# bicicletta-battery-sensor.net
KiCad netlist of a schematic drawn in EAGLE
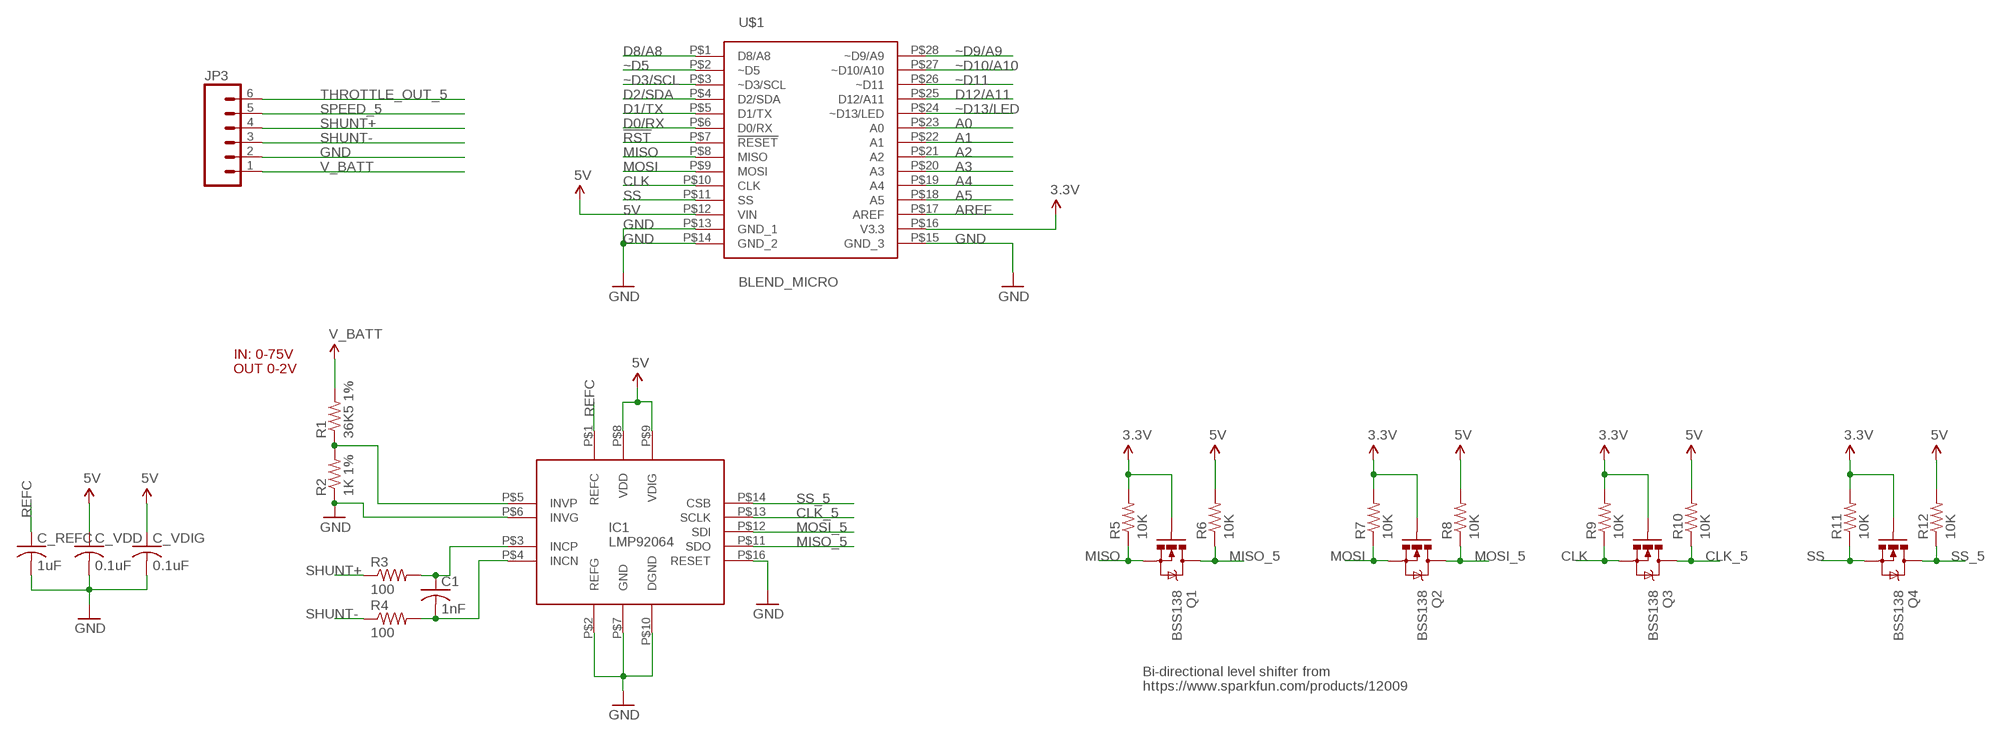
[diagram p0: schematic, sheet 1]

(export (version "E")
  (design (tool "Eeschema 10.0.6"))
  (components
    (comp (ref "C1")
      (value "1nF")
      (footprint "eagle-import:C0603")
      (libsource (lib "eagle-import") (part "C-USC0603"))
    )
    (comp (ref "C_REFC")
      (value "1uF")
      (footprint "eagle-import:C0603")
      (libsource (lib "eagle-import") (part "C-USC0603"))
    )
    (comp (ref "C_VDD")
      (value "0.1uF")
      (footprint "eagle-import:C0603")
      (libsource (lib "eagle-import") (part "C-USC0603"))
    )
    (comp (ref "C_VDIG")
      (value "0.1uF")
      (footprint "eagle-import:C0603")
      (libsource (lib "eagle-import") (part "C-USC0603"))
    )
    (comp (ref "IC1")
      (value "LMP92064")
      (footprint "eagle-import:WSON-16")
      (libsource (lib "eagle-import") (part "LMP92064"))
    )
    (comp (ref "JP3")
      (value "M06SIP")
      (footprint "eagle-import:1X06")
      (libsource (lib "eagle-import") (part "M06SIP"))
    )
    (comp (ref "Q1")
      (value "BSS138")
      (footprint "eagle-import:SOT23-3")
      (libsource (lib "eagle-import") (part "MOSFET-NCHANNELBSS138"))
    )
    (comp (ref "Q2")
      (value "BSS138")
      (footprint "eagle-import:SOT23-3")
      (libsource (lib "eagle-import") (part "MOSFET-NCHANNELBSS138"))
    )
    (comp (ref "Q3")
      (value "BSS138")
      (footprint "eagle-import:SOT23-3")
      (libsource (lib "eagle-import") (part "MOSFET-NCHANNELBSS138"))
    )
    (comp (ref "Q4")
      (value "BSS138")
      (footprint "eagle-import:SOT23-3")
      (libsource (lib "eagle-import") (part "MOSFET-NCHANNELBSS138"))
    )
    (comp (ref "R1")
      (value "36K5 1%")
      (footprint "eagle-import:R0603")
      (libsource (lib "eagle-import") (part "R-US_R0603"))
    )
    (comp (ref "R2")
      (value "1K 1%")
      (footprint "eagle-import:R0603")
      (libsource (lib "eagle-import") (part "R-US_R0603"))
    )
    (comp (ref "R3")
      (value "100")
      (footprint "eagle-import:R0603")
      (libsource (lib "eagle-import") (part "R-US_R0603"))
    )
    (comp (ref "R4")
      (value "100")
      (footprint "eagle-import:R0603")
      (libsource (lib "eagle-import") (part "R-US_R0603"))
    )
    (comp (ref "R5")
      (value "10K")
      (footprint "eagle-import:R0603")
      (libsource (lib "eagle-import") (part "R-US_R0603"))
    )
    (comp (ref "R6")
      (value "10K")
      (footprint "eagle-import:R0603")
      (libsource (lib "eagle-import") (part "R-US_R0603"))
    )
    (comp (ref "R7")
      (value "10K")
      (footprint "eagle-import:R0603")
      (libsource (lib "eagle-import") (part "R-US_R0603"))
    )
    (comp (ref "R8")
      (value "10K")
      (footprint "eagle-import:R0603")
      (libsource (lib "eagle-import") (part "R-US_R0603"))
    )
    (comp (ref "R9")
      (value "10K")
      (footprint "eagle-import:R0603")
      (libsource (lib "eagle-import") (part "R-US_R0603"))
    )
    (comp (ref "R10")
      (value "10K")
      (footprint "eagle-import:R0603")
      (libsource (lib "eagle-import") (part "R-US_R0603"))
    )
    (comp (ref "R11")
      (value "10K")
      (footprint "eagle-import:R0603")
      (libsource (lib "eagle-import") (part "R-US_R0603"))
    )
    (comp (ref "R12")
      (value "10K")
      (footprint "eagle-import:R0603")
      (libsource (lib "eagle-import") (part "R-US_R0603"))
    )
    (comp (ref "U$1")
      (value "BLEND_MICRO")
      (footprint "eagle-import:BLEND_MICRO")
      (libsource (lib "eagle-import") (part "BLEND_MICRO"))
    )
  )
  (nets
    (net (code "1") (name "/A0") (class "Default")
      (node (ref "U$1") (pin "P$23") (pinfunction "A0_P$23") (pintype "bidirectional"))
    )
    (net (code "2") (name "/A1") (class "Default")
      (node (ref "U$1") (pin "P$22") (pinfunction "A1_P$22") (pintype "bidirectional"))
    )
    (net (code "3") (name "/A2") (class "Default")
      (node (ref "U$1") (pin "P$21") (pinfunction "A2_P$21") (pintype "bidirectional"))
    )
    (net (code "4") (name "/A3") (class "Default")
      (node (ref "U$1") (pin "P$20") (pinfunction "A3_P$20") (pintype "bidirectional"))
    )
    (net (code "5") (name "/A4") (class "Default")
      (node (ref "U$1") (pin "P$19") (pinfunction "A4_P$19") (pintype "bidirectional"))
    )
    (net (code "6") (name "/A5") (class "Default")
      (node (ref "U$1") (pin "P$18") (pinfunction "A5_P$18") (pintype "bidirectional"))
    )
    (net (code "7") (name "/AREF") (class "Default")
      (node (ref "U$1") (pin "P$17") (pinfunction "AREF_P$17") (pintype "bidirectional"))
    )
    (net (code "8") (name "/CLK") (class "Default")
      (node (ref "Q3") (pin "2") (pinfunction "S_2") (pintype "passive"))
      (node (ref "R9") (pin "1") (pinfunction "1_1") (pintype "passive"))
      (node (ref "U$1") (pin "P$10") (pinfunction "CLK_P$10") (pintype "bidirectional"))
    )
    (net (code "9") (name "/CLK_5") (class "Default")
      (node (ref "IC1") (pin "P$13") (pinfunction "SCLK_P$13") (pintype "bidirectional"))
      (node (ref "Q3") (pin "3") (pinfunction "D_3") (pintype "passive"))
      (node (ref "R10") (pin "1") (pinfunction "1_1") (pintype "passive"))
    )
    (net (code "10") (name "/D0{slash}RX") (class "Default")
      (node (ref "U$1") (pin "P$6") (pinfunction "D0/RX_P$6") (pintype "bidirectional"))
    )
    (net (code "11") (name "/D1{slash}TX") (class "Default")
      (node (ref "U$1") (pin "P$5") (pinfunction "D1/TX_P$5") (pintype "bidirectional"))
    )
    (net (code "12") (name "/D2{slash}SDA") (class "Default")
      (node (ref "U$1") (pin "P$4") (pinfunction "D2/SDA_P$4") (pintype "bidirectional"))
    )
    (net (code "13") (name "/D8{slash}A8") (class "Default")
      (node (ref "U$1") (pin "P$1") (pinfunction "D8/A8_P$1") (pintype "bidirectional"))
    )
    (net (code "14") (name "/D12{slash}A11") (class "Default")
      (node (ref "U$1") (pin "P$25") (pinfunction "D12/A11_P$25") (pintype "bidirectional"))
    )
    (net (code "15") (name "/MISO") (class "Default")
      (node (ref "Q1") (pin "2") (pinfunction "S_2") (pintype "passive"))
      (node (ref "R5") (pin "1") (pinfunction "1_1") (pintype "passive"))
      (node (ref "U$1") (pin "P$8") (pinfunction "MISO_P$8") (pintype "bidirectional"))
    )
    (net (code "16") (name "/MISO_5") (class "Default")
      (node (ref "IC1") (pin "P$11") (pinfunction "SDO_P$11") (pintype "bidirectional"))
      (node (ref "Q1") (pin "3") (pinfunction "D_3") (pintype "passive"))
      (node (ref "R6") (pin "1") (pinfunction "1_1") (pintype "passive"))
    )
    (net (code "17") (name "/MOSI") (class "Default")
      (node (ref "Q2") (pin "2") (pinfunction "S_2") (pintype "passive"))
      (node (ref "R7") (pin "1") (pinfunction "1_1") (pintype "passive"))
      (node (ref "U$1") (pin "P$9") (pinfunction "MOSI_P$9") (pintype "bidirectional"))
    )
    (net (code "18") (name "/MOSI_5") (class "Default")
      (node (ref "IC1") (pin "P$12") (pinfunction "SDI_P$12") (pintype "bidirectional"))
      (node (ref "Q2") (pin "3") (pinfunction "D_3") (pintype "passive"))
      (node (ref "R8") (pin "1") (pinfunction "1_1") (pintype "passive"))
    )
    (net (code "19") (name "/REFC") (class "Default")
      (node (ref "C_REFC") (pin "1") (pinfunction "1_1") (pintype "passive"))
      (node (ref "IC1") (pin "P$1") (pinfunction "REFC_P$1") (pintype "bidirectional"))
    )
    (net (code "20") (name "/SHUNT+") (class "Default")
      (node (ref "JP3") (pin "4") (pinfunction "4_4") (pintype "passive"))
      (node (ref "R3") (pin "1") (pinfunction "1_1") (pintype "passive"))
    )
    (net (code "21") (name "/SHUNT-") (class "Default")
      (node (ref "JP3") (pin "3") (pinfunction "3_3") (pintype "passive"))
      (node (ref "R4") (pin "1") (pinfunction "1_1") (pintype "passive"))
    )
    (net (code "22") (name "/SPEED_5") (class "Default")
      (node (ref "JP3") (pin "5") (pinfunction "5_5") (pintype "passive"))
    )
    (net (code "23") (name "/SS") (class "Default")
      (node (ref "Q4") (pin "2") (pinfunction "S_2") (pintype "passive"))
      (node (ref "R11") (pin "1") (pinfunction "1_1") (pintype "passive"))
      (node (ref "U$1") (pin "P$11") (pinfunction "SS_P$11") (pintype "bidirectional"))
    )
    (net (code "24") (name "/SS_5") (class "Default")
      (node (ref "IC1") (pin "P$14") (pinfunction "CSB_P$14") (pintype "bidirectional"))
      (node (ref "Q4") (pin "3") (pinfunction "D_3") (pintype "passive"))
      (node (ref "R12") (pin "1") (pinfunction "1_1") (pintype "passive"))
    )
    (net (code "25") (name "/THROTTLE_OUT_5") (class "Default")
      (node (ref "JP3") (pin "6") (pinfunction "6_6") (pintype "passive"))
    )
    (net (code "26") (name "/~{D3{slash}SCL}") (class "Default")
      (node (ref "U$1") (pin "P$3") (pinfunction "~{D3/SCL}_P$3") (pintype "bidirectional"))
    )
    (net (code "27") (name "/~{D5}") (class "Default")
      (node (ref "U$1") (pin "P$2") (pinfunction "~{D5}_P$2") (pintype "bidirectional"))
    )
    (net (code "28") (name "/~{D9{slash}A9}") (class "Default")
      (node (ref "U$1") (pin "P$28") (pinfunction "~{D9/A9}_P$28") (pintype "bidirectional"))
    )
    (net (code "29") (name "/~{D10{slash}A10}") (class "Default")
      (node (ref "U$1") (pin "P$27") (pinfunction "~{D10/A10}_P$27") (pintype "bidirectional"))
    )
    (net (code "30") (name "/~{D11}") (class "Default")
      (node (ref "U$1") (pin "P$26") (pinfunction "~{D11}_P$26") (pintype "bidirectional"))
    )
    (net (code "31") (name "/~{D13{slash}LED}") (class "Default")
      (node (ref "U$1") (pin "P$24") (pinfunction "~{D13/LED}_P$24") (pintype "bidirectional"))
    )
    (net (code "32") (name "/~{RST}") (class "Default")
      (node (ref "U$1") (pin "P$7") (pinfunction "~{RESET}_P$7") (pintype "bidirectional"))
    )
    (net (code "33") (name "3.3V") (class "Default")
      (node (ref "Q1") (pin "1") (pinfunction "G_1") (pintype "passive"))
      (node (ref "Q2") (pin "1") (pinfunction "G_1") (pintype "passive"))
      (node (ref "Q3") (pin "1") (pinfunction "G_1") (pintype "passive"))
      (node (ref "Q4") (pin "1") (pinfunction "G_1") (pintype "passive"))
      (node (ref "R11") (pin "2") (pinfunction "2_2") (pintype "passive"))
      (node (ref "R5") (pin "2") (pinfunction "2_2") (pintype "passive"))
      (node (ref "R7") (pin "2") (pinfunction "2_2") (pintype "passive"))
      (node (ref "R9") (pin "2") (pinfunction "2_2") (pintype "passive"))
      (node (ref "U$1") (pin "P$16") (pinfunction "V3.3_P$16") (pintype "bidirectional"))
    )
    (net (code "34") (name "5V") (class "Default")
      (node (ref "C_VDD") (pin "1") (pinfunction "1_1") (pintype "passive"))
      (node (ref "C_VDIG") (pin "1") (pinfunction "1_1") (pintype "passive"))
      (node (ref "IC1") (pin "P$8") (pinfunction "VDD_P$8") (pintype "bidirectional"))
      (node (ref "IC1") (pin "P$9") (pinfunction "VDIG_P$9") (pintype "bidirectional"))
      (node (ref "R10") (pin "2") (pinfunction "2_2") (pintype "passive"))
      (node (ref "R12") (pin "2") (pinfunction "2_2") (pintype "passive"))
      (node (ref "R6") (pin "2") (pinfunction "2_2") (pintype "passive"))
      (node (ref "R8") (pin "2") (pinfunction "2_2") (pintype "passive"))
      (node (ref "U$1") (pin "P$12") (pinfunction "VIN_P$12") (pintype "bidirectional"))
    )
    (net (code "35") (name "GND") (class "Default")
      (node (ref "C_REFC") (pin "2") (pinfunction "2_2") (pintype "passive"))
      (node (ref "C_VDD") (pin "2") (pinfunction "2_2") (pintype "passive"))
      (node (ref "C_VDIG") (pin "2") (pinfunction "2_2") (pintype "passive"))
      (node (ref "IC1") (pin "P$10") (pinfunction "DGND_P$10") (pintype "bidirectional"))
      (node (ref "IC1") (pin "P$16") (pinfunction "RESET_P$16") (pintype "bidirectional"))
      (node (ref "IC1") (pin "P$2") (pinfunction "REFG_P$2") (pintype "bidirectional"))
      (node (ref "IC1") (pin "P$6") (pinfunction "INVG_P$6") (pintype "bidirectional"))
      (node (ref "IC1") (pin "P$7") (pinfunction "GND_P$7") (pintype "bidirectional"))
      (node (ref "JP3") (pin "2") (pinfunction "2_2") (pintype "passive"))
      (node (ref "R2") (pin "1") (pinfunction "1_1") (pintype "passive"))
      (node (ref "U$1") (pin "P$13") (pinfunction "GND_1_P$13") (pintype "bidirectional"))
      (node (ref "U$1") (pin "P$14") (pinfunction "GND_2_P$14") (pintype "bidirectional"))
      (node (ref "U$1") (pin "P$15") (pinfunction "GND_3_P$15") (pintype "bidirectional"))
    )
    (net (code "36") (name "Net-(IC1-INCN)") (class "Default")
      (node (ref "C1") (pin "2") (pinfunction "2_2") (pintype "passive"))
      (node (ref "IC1") (pin "P$4") (pinfunction "INCN_P$4") (pintype "bidirectional"))
      (node (ref "R4") (pin "2") (pinfunction "2_2") (pintype "passive"))
    )
    (net (code "37") (name "Net-(IC1-INCP)") (class "Default")
      (node (ref "C1") (pin "1") (pinfunction "1_1") (pintype "passive"))
      (node (ref "IC1") (pin "P$3") (pinfunction "INCP_P$3") (pintype "bidirectional"))
      (node (ref "R3") (pin "2") (pinfunction "2_2") (pintype "passive"))
    )
    (net (code "38") (name "Net-(IC1-INVP)") (class "Default")
      (node (ref "IC1") (pin "P$5") (pinfunction "INVP_P$5") (pintype "bidirectional"))
      (node (ref "R1") (pin "1") (pinfunction "1_1") (pintype "passive"))
      (node (ref "R2") (pin "2") (pinfunction "2_2") (pintype "passive"))
    )
    (net (code "39") (name "V_BATT") (class "Default")
      (node (ref "JP3") (pin "1") (pinfunction "1_1") (pintype "passive"))
      (node (ref "R1") (pin "2") (pinfunction "2_2") (pintype "passive"))
    )
  )
)
